# 09_Misc.net
KiCad netlist of a schematic drawn in Altium Designer
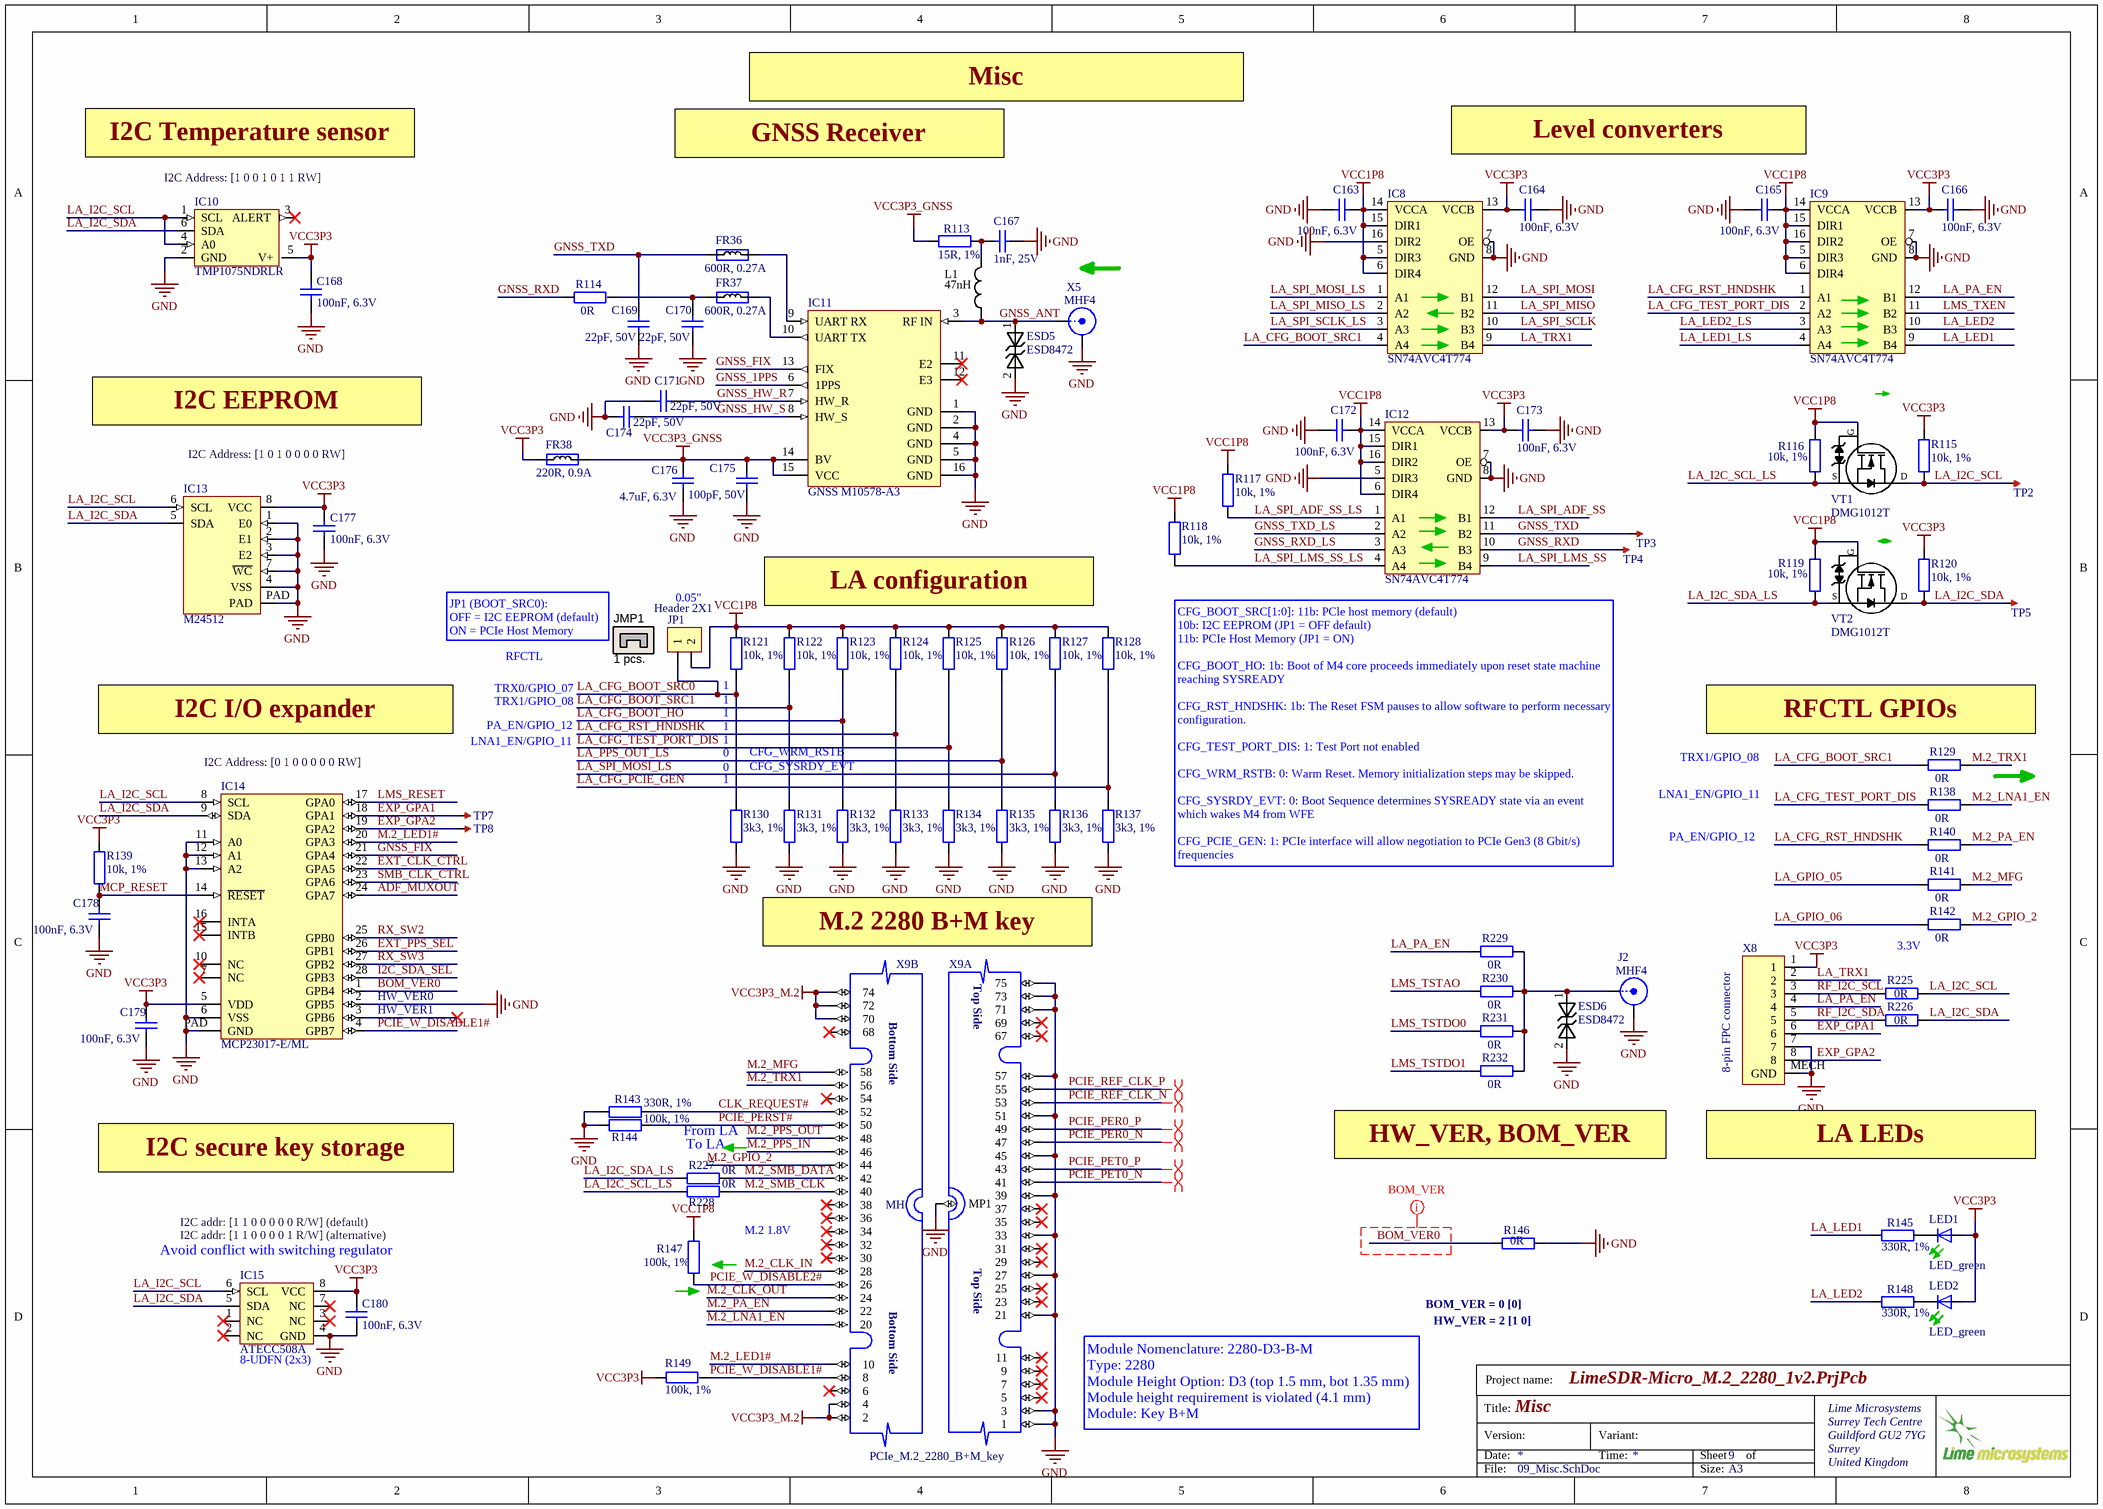
[diagram p0: 09_Misc.SchDoc]

(export (version "E")
  (design (tool "Eeschema 10.0.6"))
  (components
    (comp (ref "C163")
      (value "100nF, 6.3V")
      (footprint "CAP0201")
      (fields (field (name "MANUFACTURER") "Samsung") (field (name "TOLERANCE") "20%"))
      (libsource (lib "LimeMicroAltiumLib_schLib") (part "Cap_0402"))
    )
    (comp (ref "C164")
      (value "100nF, 6.3V")
      (footprint "CAP0201")
      (fields (field (name "MANUFACTURER") "Samsung") (field (name "TOLERANCE") "20%"))
      (libsource (lib "LimeMicroAltiumLib_schLib") (part "Cap_0402"))
    )
    (comp (ref "C165")
      (value "100nF, 6.3V")
      (footprint "CAP0201")
      (fields (field (name "MANUFACTURER") "Samsung") (field (name "TOLERANCE") "20%"))
      (libsource (lib "LimeMicroAltiumLib_schLib") (part "Cap_0402"))
    )
    (comp (ref "C166")
      (value "100nF, 6.3V")
      (footprint "CAP0201")
      (fields (field (name "MANUFACTURER") "Samsung") (field (name "TOLERANCE") "20%"))
      (libsource (lib "LimeMicroAltiumLib_schLib") (part "Cap_0402"))
    )
    (comp (ref "C167")
      (value "1nF, 25V")
      (footprint "CAP0201")
      (fields (field (name "TOLERANCE") "±10%") (field (name "MANUFACTURER") "TDK Corporation"))
      (libsource (lib "LimeMicroAltiumLib_schLib") (part "Cap_0402"))
    )
    (comp (ref "C168")
      (value "100nF, 6.3V")
      (footprint "CAP0201")
      (fields (field (name "MANUFACTURER") "Samsung") (field (name "TOLERANCE") "20%"))
      (libsource (lib "LimeMicroAltiumLib_schLib") (part "Cap_0402"))
    )
    (comp (ref "C169")
      (value "22pF, 50V")
      (footprint "CAP0201")
      (fields
        (field (name "MANUFACTURER") "Murata")
        (field (name "TOLERANCE") "5%")
        (field (name "VOLTAGE") "50V")
      )
      (libsource (lib "LimeMicroAltiumLib_schLib") (part "Cap_0402"))
    )
    (comp (ref "C170")
      (value "22pF, 50V")
      (footprint "CAP0201")
      (fields
        (field (name "MANUFACTURER") "Murata")
        (field (name "TOLERANCE") "5%")
        (field (name "VOLTAGE") "50V")
      )
      (libsource (lib "LimeMicroAltiumLib_schLib") (part "Cap_0402"))
    )
    (comp (ref "C171")
      (value "22pF, 50V")
      (footprint "CAP0201")
      (fields
        (field (name "MANUFACTURER") "Murata")
        (field (name "TOLERANCE") "5%")
        (field (name "VOLTAGE") "50V")
      )
      (libsource (lib "LimeMicroAltiumLib_schLib") (part "Cap_0402"))
    )
    (comp (ref "C172")
      (value "100nF, 6.3V")
      (footprint "CAP0201")
      (fields (field (name "MANUFACTURER") "Samsung") (field (name "TOLERANCE") "20%"))
      (libsource (lib "LimeMicroAltiumLib_schLib") (part "Cap_0402"))
    )
    (comp (ref "C173")
      (value "100nF, 6.3V")
      (footprint "CAP0201")
      (fields (field (name "MANUFACTURER") "Samsung") (field (name "TOLERANCE") "20%"))
      (libsource (lib "LimeMicroAltiumLib_schLib") (part "Cap_0402"))
    )
    (comp (ref "C174")
      (value "22pF, 50V")
      (footprint "CAP0201")
      (fields
        (field (name "MANUFACTURER") "Murata")
        (field (name "TOLERANCE") "5%")
        (field (name "VOLTAGE") "50V")
      )
      (libsource (lib "LimeMicroAltiumLib_schLib") (part "Cap_0402"))
    )
    (comp (ref "C175")
      (value "100pF, 50V")
      (footprint "CAP0201")
      (fields
        (field (name "MANUFACTURER") "TDK")
        (field (name "TOLERANCE") "5%")
        (field (name "VOLTAGE") "50V")
      )
      (libsource (lib "LimeMicroAltiumLib_schLib") (part "Cap_0402"))
    )
    (comp (ref "C176")
      (value "4.7uF, 6.3V")
      (footprint "CAP0402")
      (fields
        (field (name "MANUFACTURER") "Murata Electronics North America")
        (field (name "TOLERANCE") "±20%")
      )
      (libsource (lib "LimeMicroAltiumLib_schLib") (part "Cap_0402"))
    )
    (comp (ref "C177")
      (value "100nF, 6.3V")
      (footprint "CAP0201")
      (fields (field (name "MANUFACTURER") "Samsung") (field (name "TOLERANCE") "20%"))
      (libsource (lib "LimeMicroAltiumLib_schLib") (part "Cap_0402"))
    )
    (comp (ref "C178")
      (value "100nF, 6.3V")
      (footprint "CAP0201")
      (fields (field (name "MANUFACTURER") "Samsung") (field (name "TOLERANCE") "20%"))
      (libsource (lib "LimeMicroAltiumLib_schLib") (part "Cap_0402"))
    )
    (comp (ref "C179")
      (value "100nF, 6.3V")
      (footprint "CAP0201")
      (fields (field (name "MANUFACTURER") "Samsung") (field (name "TOLERANCE") "20%"))
      (libsource (lib "LimeMicroAltiumLib_schLib") (part "Cap_0402"))
    )
    (comp (ref "C180")
      (value "100nF, 6.3V")
      (footprint "CAP0201")
      (fields (field (name "MANUFACTURER") "Samsung") (field (name "TOLERANCE") "20%"))
      (libsource (lib "LimeMicroAltiumLib_schLib") (part "Cap_0402"))
    )
    (comp (ref "ESD5")
      (value "ESD8472")
      (footprint "ESD8472_X3DFN2")
      (fields (field (name "MANUFACTURER") "ON Semiconductor"))
      (libsource (lib "LimeMicroAltiumLib_schLib") (part "ESD8472"))
    )
    (comp (ref "ESD6")
      (value "ESD8472")
      (footprint "ESD8472_X3DFN2")
      (fields (field (name "MANUFACTURER") "ON Semiconductor"))
      (libsource (lib "LimeMicroAltiumLib_schLib") (part "ESD8472"))
    )
    (comp (ref "FR36")
      (value "600R, 0.27A")
      (footprint "RES0201")
      (fields (field (name "MANUFACTURER") "Taiyo Yuden"))
      (libsource (lib "LimeMicroAltiumLib_schLib") (part "Ferrite"))
    )
    (comp (ref "FR37")
      (value "600R, 0.27A")
      (footprint "RES0201")
      (fields (field (name "MANUFACTURER") "Taiyo Yuden"))
      (libsource (lib "LimeMicroAltiumLib_schLib") (part "Ferrite"))
    )
    (comp (ref "FR38")
      (value "220R, 0.9A")
      (footprint "RES0402")
      (fields (field (name "MANUFACTURER") "TDK Corporation"))
      (libsource (lib "LimeFPGAboard_schLib") (part "Ferrite"))
    )
    (comp (ref "IC8")
      (value "SN74AVC4T774")
      (footprint "SN74AVC4T774_v1")
      (fields (field (name "MANUFACTURER") "Texas Instruments"))
      (libsource (lib "LimeMicroAltiumLib") (part "SN74AVC4T774"))
    )
    (comp (ref "IC9")
      (value "SN74AVC4T774")
      (footprint "SN74AVC4T774_v1")
      (fields (field (name "MANUFACTURER") "Texas Instruments"))
      (libsource (lib "LimeMicroAltiumLib") (part "SN74AVC4T774"))
    )
    (comp (ref "IC10")
      (value "TMP1075NDRLR")
      (footprint "TMP1075NDRLR_temperature_sensor_SOT563")
      (fields (field (name "MANUFACTURER") "Texas Instruments"))
      (libsource (lib "LimeMicroAltiumLib_schLib_r04") (part "TMP1075NDRLR_temperature_sensor"))
    )
    (comp (ref "IC11")
      (value "GNSS M10578-A3")
      (footprint "M10578-A3_v2")
      (fields (field (name "MANUFACTURER") "Antenova"))
      (libsource (lib "LimeMicroAltiumLib_schLib_r04") (part "M10578-A3_GPS_GNSS"))
    )
    (comp (ref "IC12")
      (value "SN74AVC4T774")
      (footprint "SN74AVC4T774_v1")
      (fields (field (name "MANUFACTURER") "Texas Instruments"))
      (libsource (lib "LimeMicroAltiumLib") (part "SN74AVC4T774"))
    )
    (comp (ref "IC13")
      (value "M24512")
      (footprint "M24128-DFMC6TG")
      (fields (field (name "MANUFACTURER") "STMicroelectronics"))
      (libsource (lib "LimeMicroAltiumLib_schLib") (part "M24128-DFMC6TG"))
    )
    (comp (ref "IC14")
      (value "MCP23017-E/ML")
      (footprint "MCP23017-E/ML_QFN28")
      (fields (field (name "MANUFACTURER") "Microchip"))
      (libsource (lib "LimeMicroAltiumLib") (part "MCP23017-E/ML_I2C_expander"))
    )
    (comp (ref "IC15")
      (value "ATECC508A")
      (footprint "LimeMicroAltiumLib:ATECC508A_UDFN8_v2")
      (fields (field (name "MANUFACTURER") "Microchip"))
      (libsource (lib "LimeMicroAltiumLib_schLib_r01") (part "ATECC508A_authentication_IC"))
    )
    (comp (ref "J2")
      (value "MHF4")
      (footprint "IPEX_MHF4_conn")
      (description "IPEX MHF4 Connector Jack, Male Pin 50 Ohms Surface Mount Solder")
      (fields (field (name "MANUFACTURER") "TE Connectivity / Linx Technologies"))
      (libsource (lib "LimeMicroAltiumLib_schLib") (part "RF_IF_connector"))
    )
    (comp (ref "JMP1")
      (value "1 pcs.")
      (footprint "MECH_JUMPER_HALF_PITCH")
      (description "Shorting Jumper, 2-position, 1.27mm pitch")
      (fields (field (name "MANUFACTURER") "Sullins"))
      (libsource (lib "LimeMicroAltiumLib_schLib") (part "JUMP_2P_CONN_HEADER"))
    )
    (comp (ref "JP1")
      (value "Header 2X1")
      (footprint "HEADER_2x1_TH_HALF_PITCH")
      (fields (field (name "MANUFACTURER") "Harwin"))
      (libsource (lib "LimeMicroAltiumLib") (part "Header_2X1"))
    )
    (comp (ref "L1")
      (value "47nH")
      (footprint "RES0402")
      (fields
        (field (name "MANUFACTURER") "COILCRAFT")
        (field (name "MANUFACTURER PART NUMBER") "0402HP-47NXJLU")
      )
      (libsource (lib "LimeMicroAltiumLib_schLib") (part "Inductor_0603"))
    )
    (comp (ref "LED1")
      (value "LED_green")
      (footprint "LED0201")
      (fields (field (name "MANUFACTURER") "Kingbright"))
      (libsource (lib "LimeFPGAboard_schLib") (part "LED_green"))
    )
    (comp (ref "LED2")
      (value "LED_green")
      (footprint "LED0201")
      (fields (field (name "MANUFACTURER") "Kingbright"))
      (libsource (lib "LimeFPGAboard_schLib") (part "LED_green"))
    )
    (comp (ref "R113")
      (value "15R, 1%")
      (footprint "RES0201")
      (fields (field (name "MANUFACTURER") "Yageo") (field (name "TOLERANCE") "1%"))
      (libsource (lib "LimeFPGAboard_schLib") (part "Res_0402"))
    )
    (comp (ref "R114")
      (value "0R")
      (footprint "RES0201")
      (fields (field (name "MANUFACTURER") "Yageo") (field (name "TOLERANCE") "5%"))
      (libsource (lib "LimeFPGAboard_schLib") (part "Res_0402"))
    )
    (comp (ref "R115")
      (value "10k, 1%")
      (footprint "RES0201")
      (fields (field (name "MANUFACTURER") "Yageo") (field (name "TOLERANCE") "1%"))
      (libsource (lib "LimeFPGAboard_schLib") (part "Res_0402"))
    )
    (comp (ref "R116")
      (value "10k, 1%")
      (footprint "RES0201")
      (fields (field (name "MANUFACTURER") "Yageo") (field (name "TOLERANCE") "1%"))
      (libsource (lib "LimeFPGAboard_schLib") (part "Res_0402"))
    )
    (comp (ref "R117")
      (value "10k, 1%")
      (footprint "RES0201")
      (fields (field (name "MANUFACTURER") "Yageo") (field (name "TOLERANCE") "1%"))
      (libsource (lib "LimeFPGAboard_schLib") (part "Res_0402"))
    )
    (comp (ref "R118")
      (value "10k, 1%")
      (footprint "RES0201")
      (fields (field (name "MANUFACTURER") "Yageo") (field (name "TOLERANCE") "1%"))
      (libsource (lib "LimeFPGAboard_schLib") (part "Res_0402"))
    )
    (comp (ref "R119")
      (value "10k, 1%")
      (footprint "RES0201")
      (fields (field (name "MANUFACTURER") "Yageo") (field (name "TOLERANCE") "1%"))
      (libsource (lib "LimeFPGAboard_schLib") (part "Res_0402"))
    )
    (comp (ref "R120")
      (value "10k, 1%")
      (footprint "RES0201")
      (fields (field (name "MANUFACTURER") "Yageo") (field (name "TOLERANCE") "1%"))
      (libsource (lib "LimeFPGAboard_schLib") (part "Res_0402"))
    )
    (comp (ref "R121")
      (value "10k, 1%")
      (footprint "RES0201")
      (fields (field (name "MANUFACTURER") "Yageo") (field (name "TOLERANCE") "1%"))
      (libsource (lib "LimeFPGAboard_schLib") (part "Res_0402"))
    )
    (comp (ref "R122")
      (value "10k, 1%")
      (footprint "RES0201")
      (fields (field (name "MANUFACTURER") "Yageo") (field (name "TOLERANCE") "1%"))
      (libsource (lib "LimeFPGAboard_schLib") (part "Res_0402"))
    )
    (comp (ref "R123")
      (value "10k, 1%")
      (footprint "RES0201")
      (fields (field (name "MANUFACTURER") "Yageo") (field (name "TOLERANCE") "1%"))
      (libsource (lib "LimeFPGAboard_schLib") (part "Res_0402"))
    )
    (comp (ref "R124")
      (value "10k, 1%")
      (footprint "RES0201")
      (fields (field (name "MANUFACTURER") "Yageo") (field (name "TOLERANCE") "1%"))
      (libsource (lib "LimeFPGAboard_schLib") (part "Res_0402"))
    )
    (comp (ref "R125")
      (value "10k, 1%")
      (footprint "RES0201")
      (fields (field (name "MANUFACTURER") "Yageo") (field (name "TOLERANCE") "1%"))
      (libsource (lib "LimeFPGAboard_schLib") (part "Res_0402"))
    )
    (comp (ref "R126")
      (value "10k, 1%")
      (footprint "RES0201")
      (fields (field (name "MANUFACTURER") "Yageo") (field (name "TOLERANCE") "1%"))
      (libsource (lib "LimeFPGAboard_schLib") (part "Res_0402"))
    )
    (comp (ref "R127")
      (value "10k, 1%")
      (footprint "RES0201")
      (fields (field (name "MANUFACTURER") "Yageo") (field (name "TOLERANCE") "1%"))
      (libsource (lib "LimeFPGAboard_schLib") (part "Res_0402"))
    )
    (comp (ref "R128")
      (value "10k, 1%")
      (footprint "RES0201")
      (fields (field (name "MANUFACTURER") "Yageo") (field (name "TOLERANCE") "1%"))
      (libsource (lib "LimeFPGAboard_schLib") (part "Res_0402"))
    )
    (comp (ref "R129")
      (value "0R")
      (footprint "RES0201")
      (fields (field (name "MANUFACTURER") "Yageo") (field (name "TOLERANCE") "5%"))
      (libsource (lib "LimeFPGAboard_schLib") (part "Res_0402"))
    )
    (comp (ref "R130")
      (value "3k3, 1%")
      (footprint "RES0201")
      (fields (field (name "MANUFACTURER") "Yageo") (field (name "TOLERANCE") "1%"))
      (libsource (lib "LimeFPGAboard_schLib") (part "Res_0402"))
    )
    (comp (ref "R131")
      (value "3k3, 1%")
      (footprint "RES0201")
      (fields (field (name "MANUFACTURER") "Yageo") (field (name "TOLERANCE") "1%"))
      (libsource (lib "LimeFPGAboard_schLib") (part "Res_0402"))
    )
    (comp (ref "R132")
      (value "3k3, 1%")
      (footprint "RES0201")
      (fields (field (name "MANUFACTURER") "Yageo") (field (name "TOLERANCE") "1%"))
      (libsource (lib "LimeFPGAboard_schLib") (part "Res_0402"))
    )
    (comp (ref "R133")
      (value "3k3, 1%")
      (footprint "RES0201")
      (fields (field (name "MANUFACTURER") "Yageo") (field (name "TOLERANCE") "1%"))
      (libsource (lib "LimeFPGAboard_schLib") (part "Res_0402"))
    )
    (comp (ref "R134")
      (value "3k3, 1%")
      (footprint "RES0201")
      (fields (field (name "MANUFACTURER") "Yageo") (field (name "TOLERANCE") "1%"))
      (libsource (lib "LimeFPGAboard_schLib") (part "Res_0402"))
    )
    (comp (ref "R135")
      (value "3k3, 1%")
      (footprint "RES0201")
      (fields (field (name "MANUFACTURER") "Yageo") (field (name "TOLERANCE") "1%"))
      (libsource (lib "LimeFPGAboard_schLib") (part "Res_0402"))
    )
    (comp (ref "R136")
      (value "3k3, 1%")
      (footprint "RES0201")
      (fields (field (name "MANUFACTURER") "Yageo") (field (name "TOLERANCE") "1%"))
      (libsource (lib "LimeFPGAboard_schLib") (part "Res_0402"))
    )
    (comp (ref "R137")
      (value "3k3, 1%")
      (footprint "RES0201")
      (fields (field (name "MANUFACTURER") "Yageo") (field (name "TOLERANCE") "1%"))
      (libsource (lib "LimeFPGAboard_schLib") (part "Res_0402"))
    )
    (comp (ref "R138")
      (value "0R")
      (footprint "RES0201")
      (fields (field (name "MANUFACTURER") "Yageo") (field (name "TOLERANCE") "5%"))
      (libsource (lib "LimeFPGAboard_schLib") (part "Res_0402"))
    )
    (comp (ref "R139")
      (value "10k, 1%")
      (footprint "RES0201")
      (fields (field (name "MANUFACTURER") "Yageo") (field (name "TOLERANCE") "1%"))
      (libsource (lib "LimeFPGAboard_schLib") (part "Res_0402"))
    )
    (comp (ref "R140")
      (value "0R")
      (footprint "RES0201")
      (fields (field (name "MANUFACTURER") "Yageo") (field (name "TOLERANCE") "5%"))
      (libsource (lib "LimeFPGAboard_schLib") (part "Res_0402"))
    )
    (comp (ref "R141")
      (value "0R")
      (footprint "RES0201")
      (fields (field (name "MANUFACTURER") "Yageo") (field (name "TOLERANCE") "5%"))
      (libsource (lib "LimeFPGAboard_schLib") (part "Res_0402"))
    )
    (comp (ref "R142")
      (value "0R")
      (footprint "RES0201")
      (fields (field (name "MANUFACTURER") "Yageo") (field (name "TOLERANCE") "5%"))
      (libsource (lib "LimeFPGAboard_schLib") (part "Res_0402"))
    )
    (comp (ref "R143")
      (value "330R, 1%")
      (footprint "RES0201")
      (fields (field (name "MANUFACTURER") "Vishay Dale") (field (name "TOLERANCE") "1%"))
      (libsource (lib "LimeFPGAboard_schLib") (part "Res_0402"))
    )
    (comp (ref "R144")
      (value "100k, 1%")
      (footprint "RES0201")
      (fields (field (name "MANUFACTURER") "Yageo") (field (name "TOLERANCE") "1%"))
      (libsource (lib "LimeMicroAltiumLib_schLib") (part "Res_0402"))
    )
    (comp (ref "R145")
      (value "330R, 1%")
      (footprint "RES0201")
      (fields (field (name "MANUFACTURER") "Vishay Dale") (field (name "TOLERANCE") "1%"))
      (libsource (lib "LimeFPGAboard_schLib") (part "Res_0402"))
    )
    (comp (ref "R146")
      (value "0R")
      (footprint "RES0201")
      (fields (field (name "MANUFACTURER") "Yageo") (field (name "TOLERANCE") "5%"))
      (libsource (lib "LimeFPGAboard_schLib") (part "Res_0402"))
    )
    (comp (ref "R147")
      (value "100k, 1%")
      (footprint "RES0201")
      (fields (field (name "MANUFACTURER") "Yageo") (field (name "TOLERANCE") "1%"))
      (libsource (lib "LimeMicroAltiumLib_schLib") (part "Res_0402"))
    )
    (comp (ref "R148")
      (value "330R, 1%")
      (footprint "RES0201")
      (fields (field (name "MANUFACTURER") "Vishay Dale") (field (name "TOLERANCE") "1%"))
      (libsource (lib "LimeFPGAboard_schLib") (part "Res_0402"))
    )
    (comp (ref "R149")
      (value "100k, 1%")
      (footprint "RES0201")
      (fields (field (name "MANUFACTURER") "Yageo") (field (name "TOLERANCE") "1%"))
      (libsource (lib "LimeMicroAltiumLib_schLib") (part "Res_0402"))
    )
    (comp (ref "R225")
      (value "0R")
      (footprint "RES0201")
      (fields (field (name "MANUFACTURER") "Yageo") (field (name "TOLERANCE") "5%"))
      (libsource (lib "LimeFPGAboard_schLib") (part "Res_0402"))
    )
    (comp (ref "R226")
      (value "0R")
      (footprint "RES0201")
      (fields (field (name "MANUFACTURER") "Yageo") (field (name "TOLERANCE") "5%"))
      (libsource (lib "LimeFPGAboard_schLib") (part "Res_0402"))
    )
    (comp (ref "R227")
      (value "0R")
      (footprint "RES0201")
      (fields (field (name "MANUFACTURER") "Yageo") (field (name "TOLERANCE") "5%"))
      (libsource (lib "LimeFPGAboard_schLib") (part "Res_0402"))
    )
    (comp (ref "R228")
      (value "0R")
      (footprint "RES0201")
      (fields (field (name "MANUFACTURER") "Yageo") (field (name "TOLERANCE") "5%"))
      (libsource (lib "LimeFPGAboard_schLib") (part "Res_0402"))
    )
    (comp (ref "R229")
      (value "0R")
      (footprint "RES0201")
      (fields (field (name "MANUFACTURER") "Yageo") (field (name "TOLERANCE") "5%"))
      (libsource (lib "LimeFPGAboard_schLib") (part "Res_0402"))
    )
    (comp (ref "R230")
      (value "0R")
      (footprint "RES0201")
      (fields (field (name "MANUFACTURER") "Yageo") (field (name "TOLERANCE") "5%"))
      (libsource (lib "LimeFPGAboard_schLib") (part "Res_0402"))
    )
    (comp (ref "R231")
      (value "0R")
      (footprint "RES0201")
      (fields (field (name "MANUFACTURER") "Yageo") (field (name "TOLERANCE") "5%"))
      (libsource (lib "LimeFPGAboard_schLib") (part "Res_0402"))
    )
    (comp (ref "R232")
      (value "0R")
      (footprint "RES0201")
      (fields (field (name "MANUFACTURER") "Yageo") (field (name "TOLERANCE") "5%"))
      (libsource (lib "LimeFPGAboard_schLib") (part "Res_0402"))
    )
    (comp (ref "TP2")
      (value "TESTPOINT_PAD")
      (footprint "TP_PAD_1MM")
      (description "Test Point PCB mount Miniature White")
      (libsource (lib "LimeMicroAltiumLib_schLib_r04") (part "TESTPOINT_PAD"))
    )
    (comp (ref "TP3")
      (value "TESTPOINT_PAD")
      (footprint "TP_PAD_1MM")
      (description "Test Point PCB mount Miniature White")
      (libsource (lib "LimeMicroAltiumLib_schLib_r04") (part "TESTPOINT_PAD"))
    )
    (comp (ref "TP4")
      (value "TESTPOINT_PAD")
      (footprint "TP_PAD_1MM")
      (description "Test Point PCB mount Miniature White")
      (libsource (lib "LimeMicroAltiumLib_schLib_r04") (part "TESTPOINT_PAD"))
    )
    (comp (ref "TP5")
      (value "TESTPOINT_PAD")
      (footprint "TP_PAD_1MM")
      (description "Test Point PCB mount Miniature White")
      (libsource (lib "LimeMicroAltiumLib_schLib_r04") (part "TESTPOINT_PAD"))
    )
    (comp (ref "TP7")
      (value "TESTPOINT_PAD")
      (footprint "TP_PAD_1MM")
      (description "Test Point PCB mount Miniature White")
      (libsource (lib "LimeMicroAltiumLib_schLib_r04") (part "TESTPOINT_PAD"))
    )
    (comp (ref "TP8")
      (value "TESTPOINT_PAD")
      (footprint "TP_PAD_1MM")
      (description "Test Point PCB mount Miniature White")
      (libsource (lib "LimeMicroAltiumLib_schLib_r04") (part "TESTPOINT_PAD"))
    )
    (comp (ref "VT1")
      (value "DMG1012T")
      (footprint "SOT523")
      (fields (field (name "MANUFACTURER") "Diodes Incorporated"))
      (libsource (lib "LimeMicroAltiumLib_schLib_r01") (part "DMG1012T"))
    )
    (comp (ref "VT2")
      (value "DMG1012T")
      (footprint "SOT523")
      (fields (field (name "MANUFACTURER") "Diodes Incorporated"))
      (libsource (lib "LimeMicroAltiumLib_schLib_r01") (part "DMG1012T"))
    )
    (comp (ref "X5")
      (value "MHF4")
      (footprint "IPEX_MHF4_conn")
      (description "IPEX MHF4 Connector Jack, Male Pin 50 Ohms Surface Mount Solder")
      (fields (field (name "MANUFACTURER") "TE Connectivity / Linx Technologies"))
      (libsource (lib "LimeMicroAltiumLib_schLib") (part "RF_IF_connector"))
    )
    (comp (ref "X8")
      (value "8-pin FPC connector")
      (footprint "503480-0800_8PIN_FPC_CONN")
      (fields (field (name "MANUFACTURER") "Molex"))
      (libsource (lib "LimeMicroAltiumLib_schLib_r04") (part "503480-0800_8PIN_FPC_CONN"))
    )
    (comp (ref "X9")
      (value "PCIe_M.2_2280_B+M_key")
      (footprint "PCIe_M.2_2280_B+M_key")
      (libsource (lib "LimeMicroAltiumLib") (part "PCIe_M.2_2280_B+M_key"))
    )
  )
  (nets
    (net (code "1") (name "/ADF_MUXOUT") (class "Default")
      (node (ref "IC14") (pin "24") (pinfunction "GPA7_24") (pintype "bidirectional"))
    )
    (net (code "2") (name "/BOM_VER0") (class "Default")
      (node (ref "IC14") (pin "1") (pinfunction "GPB4_1") (pintype "bidirectional"))
      (node (ref "R146") (pin "1") (pinfunction "1_1") (pintype "passive"))
    )
    (net (code "3") (name "/CLK_REQUEST#") (class "Default")
      (node (ref "R143") (pin "1") (pinfunction "1_1") (pintype "passive"))
      (node (ref "X9") (pin "P52") (pinfunction "52_P52") (pintype "bidirectional"))
    )
    (net (code "4") (name "/EXP_GPA1") (class "Default")
      (node (ref "IC14") (pin "18") (pinfunction "GPA1_18") (pintype "bidirectional"))
      (node (ref "TP7") (pin "1") (pintype "passive"))
      (node (ref "X8") (pin "6") (pinfunction "6_6") (pintype "passive"))
    )
    (net (code "5") (name "/EXP_GPA2") (class "Default")
      (node (ref "IC14") (pin "19") (pinfunction "GPA2_19") (pintype "bidirectional"))
      (node (ref "TP8") (pin "1") (pintype "passive"))
      (node (ref "X8") (pin "8") (pinfunction "8_8") (pintype "passive"))
    )
    (net (code "6") (name "/EXT_CLK_CTRL") (class "Default")
      (node (ref "IC14") (pin "22") (pinfunction "GPA5_22") (pintype "bidirectional"))
    )
    (net (code "7") (name "/EXT_PPS_SEL") (class "Default")
      (node (ref "IC14") (pin "26") (pinfunction "GPB1_26") (pintype "bidirectional"))
    )
    (net (code "8") (name "/GNSS_1PPS") (class "Default")
      (node (ref "IC11") (pin "6") (pinfunction "1PPS_6") (pintype "output"))
    )
    (net (code "9") (name "/GNSS_ANT") (class "Default")
      (node (ref "ESD5") (pin "1") (pinfunction "1_1") (pintype "passive"))
      (node (ref "IC11") (pin "3") (pinfunction "RF_IN_3") (pintype "input"))
      (node (ref "L1") (pin "1") (pinfunction "1_1") (pintype "passive"))
      (node (ref "X5") (pin "1") (pinfunction "X_1") (pintype "passive"))
    )
    (net (code "10") (name "/GNSS_FIX") (class "Default")
      (node (ref "IC11") (pin "13") (pinfunction "FIX_13") (pintype "output"))
      (node (ref "IC14") (pin "21") (pinfunction "GPA4_21") (pintype "bidirectional"))
    )
    (net (code "11") (name "/GNSS_HW_R") (class "Default")
      (node (ref "C171") (pin "1") (pinfunction "1_1") (pintype "passive"))
      (node (ref "IC11") (pin "7") (pinfunction "HW_R_7") (pintype "input"))
    )
    (net (code "12") (name "/GNSS_HW_S") (class "Default")
      (node (ref "C174") (pin "1") (pinfunction "1_1") (pintype "passive"))
      (node (ref "IC11") (pin "8") (pinfunction "HW_S_8") (pintype "input"))
    )
    (net (code "13") (name "/GNSS_RXD") (class "Default")
      (node (ref "IC12") (pin "10") (pinfunction "B3_10") (pintype "passive"))
      (node (ref "R114") (pin "1") (pinfunction "1_1") (pintype "passive"))
      (node (ref "TP4") (pin "1") (pintype "passive"))
    )
    (net (code "14") (name "/GNSS_RXD_LS") (class "Default")
      (node (ref "IC12") (pin "3") (pinfunction "A3_3") (pintype "passive"))
    )
    (net (code "15") (name "/GNSS_TXD") (class "Default")
      (node (ref "C169") (pin "1") (pinfunction "1_1") (pintype "passive"))
      (node (ref "FR36") (pin "1") (pinfunction "1_1") (pintype "passive"))
      (node (ref "IC12") (pin "11") (pinfunction "B2_11") (pintype "passive"))
      (node (ref "TP3") (pin "1") (pintype "passive"))
    )
    (net (code "16") (name "/GNSS_TXD_LS") (class "Default")
      (node (ref "IC12") (pin "2") (pinfunction "A2_2") (pintype "passive"))
    )
    (net (code "17") (name "/I2C_SDA_SEL") (class "Default")
      (node (ref "IC14") (pin "28") (pinfunction "GPB3_28") (pintype "bidirectional"))
    )
    (net (code "18") (name "/LA_CFG_BOOT_HO") (class "Default")
      (node (ref "R123") (pin "2") (pinfunction "2_2") (pintype "passive"))
      (node (ref "R132") (pin "1") (pinfunction "1_1") (pintype "passive"))
    )
    (net (code "19") (name "/LA_CFG_BOOT_SRC0") (class "Default")
      (node (ref "JP1") (pin "1") (pinfunction "1_1") (pintype "passive"))
      (node (ref "R121") (pin "2") (pinfunction "2_2") (pintype "passive"))
      (node (ref "R130") (pin "1") (pinfunction "1_1") (pintype "passive"))
    )
    (net (code "20") (name "/LA_CFG_BOOT_SRC1") (class "Default")
      (node (ref "IC8") (pin "4") (pinfunction "A4_4") (pintype "passive"))
      (node (ref "R122") (pin "2") (pinfunction "2_2") (pintype "passive"))
      (node (ref "R129") (pin "1") (pinfunction "1_1") (pintype "passive"))
      (node (ref "R131") (pin "1") (pinfunction "1_1") (pintype "passive"))
    )
    (net (code "21") (name "/LA_CFG_PCIE_GEN") (class "Default")
      (node (ref "R128") (pin "2") (pinfunction "2_2") (pintype "passive"))
      (node (ref "R137") (pin "1") (pinfunction "1_1") (pintype "passive"))
    )
    (net (code "22") (name "/LA_CFG_RST_HNDSHK") (class "Default")
      (node (ref "IC9") (pin "1") (pinfunction "A1_1") (pintype "passive"))
      (node (ref "R124") (pin "2") (pinfunction "2_2") (pintype "passive"))
      (node (ref "R133") (pin "1") (pinfunction "1_1") (pintype "passive"))
      (node (ref "R140") (pin "1") (pinfunction "1_1") (pintype "passive"))
    )
    (net (code "23") (name "/LA_CFG_TEST_PORT_DIS") (class "Default")
      (node (ref "IC9") (pin "2") (pinfunction "A2_2") (pintype "passive"))
      (node (ref "R125") (pin "2") (pinfunction "2_2") (pintype "passive"))
      (node (ref "R134") (pin "1") (pinfunction "1_1") (pintype "passive"))
      (node (ref "R138") (pin "1") (pinfunction "1_1") (pintype "passive"))
    )
    (net (code "24") (name "/LA_GPIO_05") (class "Default")
      (node (ref "R141") (pin "1") (pinfunction "1_1") (pintype "passive"))
    )
    (net (code "25") (name "/LA_GPIO_06") (class "Default")
      (node (ref "R142") (pin "1") (pinfunction "1_1") (pintype "passive"))
    )
    (net (code "26") (name "/LA_I2C_SCL") (class "Default")
      (node (ref "IC10") (pin "1") (pinfunction "SCL_1") (pintype "input"))
      (node (ref "IC10") (pin "4") (pinfunction "A0_4") (pintype "input"))
      (node (ref "IC13") (pin "6") (pinfunction "SCL_6") (pintype "input"))
      (node (ref "IC14") (pin "8") (pinfunction "SCL_8") (pintype "input"))
      (node (ref "IC15") (pin "6") (pinfunction "SCL_6") (pintype "input"))
      (node (ref "R115") (pin "2") (pinfunction "2_2") (pintype "passive"))
      (node (ref "R225") (pin "2") (pinfunction "2_2") (pintype "passive"))
      (node (ref "TP2") (pin "1") (pintype "passive"))
      (node (ref "VT1") (pin "D") (pinfunction "D_D") (pintype "passive"))
    )
    (net (code "27") (name "/LA_I2C_SCL_LS") (class "Default")
      (node (ref "R116") (pin "2") (pinfunction "2_2") (pintype "passive"))
      (node (ref "R228") (pin "1") (pinfunction "1_1") (pintype "passive"))
      (node (ref "VT1") (pin "S") (pinfunction "S_S") (pintype "passive"))
    )
    (net (code "28") (name "/LA_I2C_SDA") (class "Default")
      (node (ref "IC10") (pin "6") (pinfunction "SDA_6") (pintype "bidirectional"))
      (node (ref "IC13") (pin "5") (pinfunction "SDA_5") (pintype "bidirectional"))
      (node (ref "IC14") (pin "9") (pinfunction "SDA_9") (pintype "bidirectional"))
      (node (ref "IC15") (pin "5") (pinfunction "SDA_5") (pintype "bidirectional"))
      (node (ref "R120") (pin "2") (pinfunction "2_2") (pintype "passive"))
      (node (ref "R226") (pin "2") (pinfunction "2_2") (pintype "passive"))
      (node (ref "TP5") (pin "1") (pintype "passive"))
      (node (ref "VT2") (pin "D") (pinfunction "D_D") (pintype "passive"))
    )
    (net (code "29") (name "/LA_I2C_SDA_LS") (class "Default")
      (node (ref "R119") (pin "2") (pinfunction "2_2") (pintype "passive"))
      (node (ref "R227") (pin "1") (pinfunction "1_1") (pintype "passive"))
      (node (ref "VT2") (pin "S") (pinfunction "S_S") (pintype "passive"))
    )
    (net (code "30") (name "/LA_LED1") (class "Default")
      (node (ref "IC9") (pin "9") (pinfunction "B4_9") (pintype "passive"))
      (node (ref "R145") (pin "2") (pinfunction "2_2") (pintype "passive"))
    )
    (net (code "31") (name "/LA_LED1_LS") (class "Default")
      (node (ref "IC9") (pin "4") (pinfunction "A4_4") (pintype "passive"))
    )
    (net (code "32") (name "/LA_LED2") (class "Default")
      (node (ref "IC9") (pin "10") (pinfunction "B3_10") (pintype "passive"))
      (node (ref "R148") (pin "2") (pinfunction "2_2") (pintype "passive"))
    )
    (net (code "33") (name "/LA_LED2_LS") (class "Default")
      (node (ref "IC9") (pin "3") (pinfunction "A3_3") (pintype "passive"))
    )
    (net (code "34") (name "/LA_PA_EN") (class "Default")
      (node (ref "IC9") (pin "12") (pinfunction "B1_12") (pintype "passive"))
      (node (ref "R229") (pin "1") (pinfunction "1_1") (pintype "passive"))
      (node (ref "X8") (pin "4") (pinfunction "4_4") (pintype "passive"))
    )
    (net (code "35") (name "/LA_PPS_OUT_LS") (class "Default")
      (node (ref "R126") (pin "2") (pinfunction "2_2") (pintype "passive"))
      (node (ref "R135") (pin "1") (pinfunction "1_1") (pintype "passive"))
    )
    (net (code "36") (name "/LA_SPI_ADF_SS") (class "Default")
      (node (ref "IC12") (pin "12") (pinfunction "B1_12") (pintype "passive"))
    )
    (net (code "37") (name "/LA_SPI_ADF_SS_LS") (class "Default")
      (node (ref "IC12") (pin "1") (pinfunction "A1_1") (pintype "passive"))
      (node (ref "R117") (pin "2") (pinfunction "2_2") (pintype "passive"))
    )
    (net (code "38") (name "/LA_SPI_LMS_SS") (class "Default")
      (node (ref "IC12") (pin "9") (pinfunction "B4_9") (pintype "passive"))
    )
    (net (code "39") (name "/LA_SPI_LMS_SS_LS") (class "Default")
      (node (ref "IC12") (pin "4") (pinfunction "A4_4") (pintype "passive"))
      (node (ref "R118") (pin "2") (pinfunction "2_2") (pintype "passive"))
    )
    (net (code "40") (name "/LA_SPI_MISO") (class "Default")
      (node (ref "IC8") (pin "11") (pinfunction "B2_11") (pintype "passive"))
    )
    (net (code "41") (name "/LA_SPI_MISO_LS") (class "Default")
      (node (ref "IC8") (pin "2") (pinfunction "A2_2") (pintype "passive"))
    )
    (net (code "42") (name "/LA_SPI_MOSI") (class "Default")
      (node (ref "IC8") (pin "12") (pinfunction "B1_12") (pintype "passive"))
    )
    (net (code "43") (name "/LA_SPI_MOSI_LS") (class "Default")
      (node (ref "IC8") (pin "1") (pinfunction "A1_1") (pintype "passive"))
      (node (ref "R127") (pin "2") (pinfunction "2_2") (pintype "passive"))
      (node (ref "R136") (pin "1") (pinfunction "1_1") (pintype "passive"))
    )
    (net (code "44") (name "/LA_SPI_SCLK") (class "Default")
      (node (ref "IC8") (pin "10") (pinfunction "B3_10") (pintype "passive"))
    )
    (net (code "45") (name "/LA_SPI_SCLK_LS") (class "Default")
      (node (ref "IC8") (pin "3") (pinfunction "A3_3") (pintype "passive"))
    )
    (net (code "46") (name "/LA_TRX1") (class "Default")
      (node (ref "IC8") (pin "9") (pinfunction "B4_9") (pintype "passive"))
      (node (ref "X8") (pin "2") (pinfunction "2_2") (pintype "passive"))
    )
    (net (code "47") (name "/LMS_RESET") (class "Default")
      (node (ref "IC14") (pin "17") (pinfunction "GPA0_17") (pintype "bidirectional"))
    )
    (net (code "48") (name "/LMS_TSTAO") (class "Default")
      (node (ref "R230") (pin "1") (pinfunction "1_1") (pintype "passive"))
    )
    (net (code "49") (name "/LMS_TSTDO0") (class "Default")
      (node (ref "R231") (pin "1") (pinfunction "1_1") (pintype "passive"))
    )
    (net (code "50") (name "/LMS_TSTDO1") (class "Default")
      (node (ref "R232") (pin "1") (pinfunction "1_1") (pintype "passive"))
    )
    (net (code "51") (name "/LMS_TXEN") (class "Default")
      (node (ref "IC9") (pin "11") (pinfunction "B2_11") (pintype "passive"))
    )
    (net (code "52") (name "/M.2_CLK_IN") (class "Default")
      (node (ref "X9") (pin "P28") (pinfunction "28_P28") (pintype "bidirectional"))
    )
    (net (code "53") (name "/M.2_CLK_OUT") (class "Default")
      (node (ref "X9") (pin "P24") (pinfunction "24_P24") (pintype "bidirectional"))
    )
    (net (code "54") (name "/M.2_GPIO_2") (class "Default")
      (node (ref "R142") (pin "2") (pinfunction "2_2") (pintype "passive"))
      (node (ref "X9") (pin "P44") (pinfunction "44_P44") (pintype "bidirectional"))
    )
    (net (code "55") (name "/M.2_LED1#") (class "Default")
      (node (ref "IC14") (pin "20") (pinfunction "GPA3_20") (pintype "bidirectional"))
      (node (ref "X9") (pin "P10") (pinfunction "10_P10") (pintype "bidirectional"))
    )
    (net (code "56") (name "/M.2_LNA1_EN") (class "Default")
      (node (ref "R138") (pin "2") (pinfunction "2_2") (pintype "passive"))
      (node (ref "X9") (pin "P20") (pinfunction "20_P20") (pintype "bidirectional"))
    )
    (net (code "57") (name "/M.2_MFG") (class "Default")
      (node (ref "R141") (pin "2") (pinfunction "2_2") (pintype "passive"))
      (node (ref "X9") (pin "P58") (pinfunction "58_P58") (pintype "bidirectional"))
    )
    (net (code "58") (name "/M.2_PA_EN") (class "Default")
      (node (ref "R140") (pin "2") (pinfunction "2_2") (pintype "passive"))
      (node (ref "X9") (pin "P22") (pinfunction "22_P22") (pintype "bidirectional"))
    )
    (net (code "59") (name "/M.2_PPS_IN") (class "Default")
      (node (ref "X9") (pin "P46") (pinfunction "46_P46") (pintype "bidirectional"))
    )
    (net (code "60") (name "/M.2_PPS_OUT") (class "Default")
      (node (ref "X9") (pin "P48") (pinfunction "48_P48") (pintype "bidirectional"))
    )
    (net (code "61") (name "/M.2_SMB_CLK") (class "Default")
      (node (ref "R228") (pin "2") (pinfunction "2_2") (pintype "passive"))
      (node (ref "X9") (pin "P40") (pinfunction "40_P40") (pintype "bidirectional"))
    )
    (net (code "62") (name "/M.2_SMB_DATA") (class "Default")
      (node (ref "R227") (pin "2") (pinfunction "2_2") (pintype "passive"))
      (node (ref "X9") (pin "P42") (pinfunction "42_P42") (pintype "bidirectional"))
    )
    (net (code "63") (name "/M.2_TRX1") (class "Default")
      (node (ref "R129") (pin "2") (pinfunction "2_2") (pintype "passive"))
      (node (ref "X9") (pin "P56") (pinfunction "56_P56") (pintype "bidirectional"))
    )
    (net (code "64") (name "/MCP_RESET") (class "Default")
      (node (ref "C178") (pin "1") (pinfunction "1_1") (pintype "passive"))
      (node (ref "IC14") (pin "14") (pinfunction "~{RESET}_14") (pintype "input"))
      (node (ref "R139") (pin "2") (pinfunction "2_2") (pintype "passive"))
    )
    (net (code "65") (name "/PCIE_PER0_N") (class "Default")
      (node (ref "X9") (pin "P47") (pinfunction "47_P47") (pintype "bidirectional"))
    )
    (net (code "66") (name "/PCIE_PER0_P") (class "Default")
      (node (ref "X9") (pin "P49") (pinfunction "49_P49") (pintype "bidirectional"))
    )
    (net (code "67") (name "/PCIE_PERST#") (class "Default")
      (node (ref "R144") (pin "1") (pinfunction "1_1") (pintype "passive"))
      (node (ref "X9") (pin "P50") (pinfunction "50_P50") (pintype "bidirectional"))
    )
    (net (code "68") (name "/PCIE_PET0_N") (class "Default")
      (node (ref "X9") (pin "P41") (pinfunction "41_P41") (pintype "bidirectional"))
    )
    (net (code "69") (name "/PCIE_PET0_P") (class "Default")
      (node (ref "X9") (pin "P43") (pinfunction "43_P43") (pintype "bidirectional"))
    )
    (net (code "70") (name "/PCIE_REF_CLK_N") (class "Default")
      (node (ref "X9") (pin "P53") (pinfunction "53_P53") (pintype "bidirectional"))
    )
    (net (code "71") (name "/PCIE_REF_CLK_P") (class "Default")
      (node (ref "X9") (pin "P55") (pinfunction "55_P55") (pintype "bidirectional"))
    )
    (net (code "72") (name "/PCIE_W_DISABLE1#") (class "Default")
      (node (ref "IC14") (pin "4") (pinfunction "GPB7_4") (pintype "bidirectional"))
      (node (ref "R149") (pin "2") (pinfunction "2_2") (pintype "passive"))
      (node (ref "X9") (pin "P8") (pinfunction "8_P8") (pintype "bidirectional"))
    )
    (net (code "73") (name "/PCIE_W_DISABLE2#") (class "Default")
      (node (ref "R147") (pin "2") (pinfunction "2_2") (pintype "passive"))
      (node (ref "X9") (pin "P26") (pinfunction "26_P26") (pintype "bidirectional"))
    )
    (net (code "74") (name "/RF_I2C_SCL") (class "Default")
      (node (ref "R225") (pin "1") (pinfunction "1_1") (pintype "passive"))
      (node (ref "X8") (pin "3") (pinfunction "3_3") (pintype "passive"))
    )
    (net (code "75") (name "/RF_I2C_SDA") (class "Default")
      (node (ref "R226") (pin "1") (pinfunction "1_1") (pintype "passive"))
      (node (ref "X8") (pin "5") (pinfunction "5_5") (pintype "passive"))
    )
    (net (code "76") (name "/RX_SW2") (class "Default")
      (node (ref "IC14") (pin "25") (pinfunction "GPB0_25") (pintype "bidirectional"))
    )
    (net (code "77") (name "/RX_SW3") (class "Default")
      (node (ref "IC14") (pin "27") (pinfunction "GPB2_27") (pintype "bidirectional"))
    )
    (net (code "78") (name "/SMB_CLK_CTRL") (class "Default")
      (node (ref "IC14") (pin "23") (pinfunction "GPA6_23") (pintype "bidirectional"))
    )
    (net (code "79") (name "GND") (class "Default")
      (node (ref "C163") (pin "1") (pinfunction "1_1") (pintype "passive"))
      (node (ref "C164") (pin "2") (pinfunction "2_2") (pintype "passive"))
      (node (ref "C165") (pin "1") (pinfunction "1_1") (pintype "passive"))
      (node (ref "C166") (pin "2") (pinfunction "2_2") (pintype "passive"))
      (node (ref "C167") (pin "2") (pinfunction "2_2") (pintype "passive"))
      (node (ref "C168") (pin "2") (pinfunction "2_2") (pintype "passive"))
      (node (ref "C169") (pin "2") (pinfunction "2_2") (pintype "passive"))
      (node (ref "C170") (pin "2") (pinfunction "2_2") (pintype "passive"))
      (node (ref "C171") (pin "2") (pinfunction "2_2") (pintype "passive"))
      (node (ref "C172") (pin "1") (pinfunction "1_1") (pintype "passive"))
      (node (ref "C173") (pin "2") (pinfunction "2_2") (pintype "passive"))
      (node (ref "C174") (pin "2") (pinfunction "2_2") (pintype "passive"))
      (node (ref "C175") (pin "1") (pinfunction "1_1") (pintype "passive"))
      (node (ref "C176") (pin "1") (pinfunction "1_1") (pintype "passive"))
      (node (ref "C177") (pin "2") (pinfunction "2_2") (pintype "passive"))
      (node (ref "C178") (pin "2") (pinfunction "2_2") (pintype "passive"))
      (node (ref "C179") (pin "2") (pinfunction "2_2") (pintype "passive"))
      (node (ref "C180") (pin "2") (pinfunction "2_2") (pintype "passive"))
      (node (ref "ESD5") (pin "2") (pinfunction "2_2") (pintype "passive"))
      (node (ref "ESD6") (pin "2") (pinfunction "2_2") (pintype "passive"))
      (node (ref "IC10") (pin "2") (pinfunction "GND_2") (pintype "passive"))
      (node (ref "IC11") (pin "1") (pinfunction "GND_1") (pintype "passive"))
      (node (ref "IC11") (pin "16") (pinfunction "GND_16") (pintype "passive"))
      (node (ref "IC11") (pin "2") (pinfunction "GND_2") (pintype "passive"))
      (node (ref "IC11") (pin "4") (pinfunction "GND_4") (pintype "passive"))
      (node (ref "IC11") (pin "5") (pinfunction "GND_5") (pintype "passive"))
      (node (ref "IC12") (pin "5") (pinfunction "DIR3_5") (pintype "passive"))
      (node (ref "IC12") (pin "7") (pinfunction "OE_7") (pintype "passive"))
      (node (ref "IC12") (pin "8") (pinfunction "GND_8") (pintype "passive"))
      (node (ref "IC13") (pin "1") (pinfunction "E0_1") (pintype "input"))
      (node (ref "IC13") (pin "2") (pinfunction "E1_2") (pintype "input"))
      (node (ref "IC13") (pin "3") (pinfunction "E2_3") (pintype "input"))
      (node (ref "IC13") (pin "4") (pinfunction "VSS_4") (pintype "power_in"))
      (node (ref "IC13") (pin "7") (pinfunction "~{WC}_7") (pintype "input"))
      (node (ref "IC13") (pin "PAD") (pinfunction "PAD_PAD") (pintype "power_in"))
      (node (ref "IC14") (pin "11") (pinfunction "A0_11") (pintype "input"))
      (node (ref "IC14") (pin "12") (pinfunction "A1_12") (pintype "input"))
      (node (ref "IC14") (pin "13") (pinfunction "A2_13") (pintype "input"))
      (node (ref "IC14") (pin "2") (pinfunction "GPB5_2") (pintype "bidirectional"))
      (node (ref "IC14") (pin "6") (pinfunction "VSS_6") (pintype "power_in"))
      (node (ref "IC14") (pin "PAD") (pinfunction "GND_PAD") (pintype "passive"))
      (node (ref "IC15") (pin "4") (pinfunction "GND_4") (pintype "passive"))
      (node (ref "IC8") (pin "16") (pinfunction "DIR2_16") (pintype "passive"))
      (node (ref "IC8") (pin "7") (pinfunction "OE_7") (pintype "passive"))
      (node (ref "IC8") (pin "8") (pinfunction "GND_8") (pintype "passive"))
      (node (ref "IC9") (pin "7") (pinfunction "OE_7") (pintype "passive"))
      (node (ref "IC9") (pin "8") (pinfunction "GND_8") (pintype "passive"))
      (node (ref "J2") (pin "2") (pinfunction "Y_2") (pintype "passive"))
      (node (ref "R130") (pin "2") (pinfunction "2_2") (pintype "passive"))
      (node (ref "R131") (pin "2") (pinfunction "2_2") (pintype "passive"))
      (node (ref "R132") (pin "2") (pinfunction "2_2") (pintype "passive"))
      (node (ref "R133") (pin "2") (pinfunction "2_2") (pintype "passive"))
      (node (ref "R134") (pin "2") (pinfunction "2_2") (pintype "passive"))
      (node (ref "R135") (pin "2") (pinfunction "2_2") (pintype "passive"))
      (node (ref "R136") (pin "2") (pinfunction "2_2") (pintype "passive"))
      (node (ref "R137") (pin "2") (pinfunction "2_2") (pintype "passive"))
      (node (ref "R143") (pin "2") (pinfunction "2_2") (pintype "passive"))
      (node (ref "R144") (pin "2") (pinfunction "2_2") (pintype "passive"))
      (node (ref "R146") (pin "2") (pinfunction "2_2") (pintype "passive"))
      (node (ref "X5") (pin "2") (pinfunction "Y_2") (pintype "passive"))
      (node (ref "X8") (pin "7") (pinfunction "7_7") (pintype "passive"))
      (node (ref "X8") (pin "MECH") (pinfunction "GND_MECH") (pintype "passive"))
      (node (ref "X9") (pin "MOUNTING-HOLE") (pinfunction "MP1_MOUNTING-HOLE") (pintype "bidirectional"))
      (node (ref "X9") (pin "P1") (pinfunction "1_P1") (pintype "bidirectional"))
      (node (ref "X9") (pin "P21") (pinfunction "21_P21") (pintype "bidirectional"))
      (node (ref "X9") (pin "P27") (pinfunction "27_P27") (pintype "bidirectional"))
      (node (ref "X9") (pin "P3") (pinfunction "3_P3") (pintype "bidirectional"))
      (node (ref "X9") (pin "P33") (pinfunction "33_P33") (pintype "bidirectional"))
      (node (ref "X9") (pin "P39") (pinfunction "39_P39") (pintype "bidirectional"))
      (node (ref "X9") (pin "P45") (pinfunction "45_P45") (pintype "bidirectional"))
      (node (ref "X9") (pin "P51") (pinfunction "51_P51") (pintype "bidirectional"))
      (node (ref "X9") (pin "P57") (pinfunction "57_P57") (pintype "bidirectional"))
      (node (ref "X9") (pin "P71") (pinfunction "71_P71") (pintype "bidirectional"))
      (node (ref "X9") (pin "P73") (pinfunction "73_P73") (pintype "bidirectional"))
      (node (ref "X9") (pin "P75") (pinfunction "75_P75") (pintype "bidirectional"))
    )
    (net (code "80") (name "Net-(C167-Pad1)") (class "Default")
      (node (ref "C167") (pin "1") (pinfunction "1_1") (pintype "passive"))
      (node (ref "L1") (pin "2") (pinfunction "2_2") (pintype "passive"))
      (node (ref "R113") (pin "1") (pinfunction "1_1") (pintype "passive"))
    )
    (net (code "81") (name "Net-(C170-Pad1)") (class "Default")
      (node (ref "C170") (pin "1") (pinfunction "1_1") (pintype "passive"))
      (node (ref "FR37") (pin "1") (pinfunction "1_1") (pintype "passive"))
      (node (ref "R114") (pin "2") (pinfunction "2_2") (pintype "passive"))
    )
    (net (code "82") (name "Net-(IC11-UART_RX)") (class "Default")
      (node (ref "FR36") (pin "2") (pinfunction "2_2") (pintype "passive"))
      (node (ref "IC11") (pin "9") (pinfunction "UART_RX_9") (pintype "input"))
    )
    (net (code "83") (name "Net-(IC11-UART_TX)") (class "Default")
      (node (ref "FR37") (pin "2") (pinfunction "2_2") (pintype "passive"))
      (node (ref "IC11") (pin "10") (pinfunction "UART_TX_10") (pintype "output"))
    )
    (net (code "84") (name "Net-(J2-X)") (class "Default")
      (node (ref "ESD6") (pin "1") (pinfunction "1_1") (pintype "passive"))
      (node (ref "J2") (pin "1") (pinfunction "X_1") (pintype "passive"))
      (node (ref "R229") (pin "2") (pinfunction "2_2") (pintype "passive"))
      (node (ref "R230") (pin "2") (pinfunction "2_2") (pintype "passive"))
      (node (ref "R231") (pin "2") (pinfunction "2_2") (pintype "passive"))
      (node (ref "R232") (pin "2") (pinfunction "2_2") (pintype "passive"))
    )
    (net (code "85") (name "Net-(LED1-C)") (class "Default")
      (node (ref "LED1") (pin "K") (pinfunction "C_K") (pintype "power_in"))
      (node (ref "R145") (pin "1") (pinfunction "1_1") (pintype "passive"))
    )
    (net (code "86") (name "Net-(LED2-C)") (class "Default")
      (node (ref "LED2") (pin "K") (pinfunction "C_K") (pintype "power_in"))
      (node (ref "R148") (pin "1") (pinfunction "1_1") (pintype "passive"))
    )
    (net (code "87") (name "VCC1P8") (class "Default")
      (node (ref "C163") (pin "2") (pinfunction "2_2") (pintype "passive"))
      (node (ref "C165") (pin "2") (pinfunction "2_2") (pintype "passive"))
      (node (ref "C172") (pin "2") (pinfunction "2_2") (pintype "passive"))
      (node (ref "IC12") (pin "14") (pinfunction "VCCA_14") (pintype "passive"))
      (node (ref "IC12") (pin "15") (pinfunction "DIR1_15") (pintype "passive"))
      (node (ref "IC12") (pin "16") (pinfunction "DIR2_16") (pintype "passive"))
      (node (ref "IC12") (pin "6") (pinfunction "DIR4_6") (pintype "passive"))
      (node (ref "IC8") (pin "14") (pinfunction "VCCA_14") (pintype "passive"))
      (node (ref "IC8") (pin "15") (pinfunction "DIR1_15") (pintype "passive"))
      (node (ref "IC8") (pin "5") (pinfunction "DIR3_5") (pintype "passive"))
      (node (ref "IC8") (pin "6") (pinfunction "DIR4_6") (pintype "passive"))
      (node (ref "IC9") (pin "14") (pinfunction "VCCA_14") (pintype "passive"))
      (node (ref "IC9") (pin "15") (pinfunction "DIR1_15") (pintype "passive"))
      (node (ref "IC9") (pin "16") (pinfunction "DIR2_16") (pintype "passive"))
      (node (ref "IC9") (pin "5") (pinfunction "DIR3_5") (pintype "passive"))
      (node (ref "IC9") (pin "6") (pinfunction "DIR4_6") (pintype "passive"))
      (node (ref "JP1") (pin "2") (pinfunction "2_2") (pintype "passive"))
      (node (ref "R116") (pin "1") (pinfunction "1_1") (pintype "passive"))
      (node (ref "R117") (pin "1") (pinfunction "1_1") (pintype "passive"))
      (node (ref "R118") (pin "1") (pinfunction "1_1") (pintype "passive"))
      (node (ref "R119") (pin "1") (pinfunction "1_1") (pintype "passive"))
      (node (ref "R121") (pin "1") (pinfunction "1_1") (pintype "passive"))
      (node (ref "R122") (pin "1") (pinfunction "1_1") (pintype "passive"))
      (node (ref "R123") (pin "1") (pinfunction "1_1") (pintype "passive"))
      (node (ref "R124") (pin "1") (pinfunction "1_1") (pintype "passive"))
      (node (ref "R125") (pin "1") (pinfunction "1_1") (pintype "passive"))
      (node (ref "R126") (pin "1") (pinfunction "1_1") (pintype "passive"))
      (node (ref "R127") (pin "1") (pinfunction "1_1") (pintype "passive"))
      (node (ref "R128") (pin "1") (pinfunction "1_1") (pintype "passive"))
      (node (ref "R147") (pin "1") (pinfunction "1_1") (pintype "passive"))
      (node (ref "VT1") (pin "G") (pinfunction "G_G") (pintype "passive"))
      (node (ref "VT2") (pin "G") (pinfunction "G_G") (pintype "passive"))
    )
    (net (code "88") (name "VCC3P3") (class "Default")
      (node (ref "C164") (pin "1") (pinfunction "1_1") (pintype "passive"))
      (node (ref "C166") (pin "1") (pinfunction "1_1") (pintype "passive"))
      (node (ref "C168") (pin "1") (pinfunction "1_1") (pintype "passive"))
      (node (ref "C173") (pin "1") (pinfunction "1_1") (pintype "passive"))
      (node (ref "C177") (pin "1") (pinfunction "1_1") (pintype "passive"))
      (node (ref "C179") (pin "1") (pinfunction "1_1") (pintype "passive"))
      (node (ref "C180") (pin "1") (pinfunction "1_1") (pintype "passive"))
      (node (ref "FR38") (pin "1") (pinfunction "1_1") (pintype "passive"))
      (node (ref "IC10") (pin "5") (pinfunction "V+_5") (pintype "power_in"))
      (node (ref "IC12") (pin "13") (pinfunction "VCCB_13") (pintype "passive"))
      (node (ref "IC13") (pin "8") (pinfunction "VCC_8") (pintype "power_in"))
      (node (ref "IC14") (pin "5") (pinfunction "VDD_5") (pintype "power_in"))
      (node (ref "IC15") (pin "8") (pinfunction "VCC_8") (pintype "power_in"))
      (node (ref "IC8") (pin "13") (pinfunction "VCCB_13") (pintype "passive"))
      (node (ref "IC9") (pin "13") (pinfunction "VCCB_13") (pintype "passive"))
      (node (ref "LED1") (pin "A") (pinfunction "A_A") (pintype "power_in"))
      (node (ref "LED2") (pin "A") (pinfunction "A_A") (pintype "power_in"))
      (node (ref "R115") (pin "1") (pinfunction "1_1") (pintype "passive"))
      (node (ref "R120") (pin "1") (pinfunction "1_1") (pintype "passive"))
      (node (ref "R139") (pin "1") (pinfunction "1_1") (pintype "passive"))
      (node (ref "R149") (pin "1") (pinfunction "1_1") (pintype "passive"))
      (node (ref "X8") (pin "1") (pinfunction "1_1") (pintype "passive"))
    )
    (net (code "89") (name "VCC3P3_GNSS") (class "Default")
      (node (ref "C175") (pin "2") (pinfunction "2_2") (pintype "passive"))
      (node (ref "C176") (pin "2") (pinfunction "2_2") (pintype "passive"))
      (node (ref "FR38") (pin "2") (pinfunction "2_2") (pintype "passive"))
      (node (ref "IC11") (pin "14") (pinfunction "BV_14") (pintype "power_in"))
      (node (ref "IC11") (pin "15") (pinfunction "VCC_15") (pintype "power_in"))
      (node (ref "R113") (pin "2") (pinfunction "2_2") (pintype "passive"))
    )
    (net (code "90") (name "VCC3P3_M.2") (class "Default")
      (node (ref "X9") (pin "P2") (pinfunction "2_P2") (pintype "bidirectional"))
      (node (ref "X9") (pin "P4") (pinfunction "4_P4") (pintype "bidirectional"))
      (node (ref "X9") (pin "P70") (pinfunction "70_P70") (pintype "bidirectional"))
      (node (ref "X9") (pin "P72") (pinfunction "72_P72") (pintype "bidirectional"))
      (node (ref "X9") (pin "P74") (pinfunction "74_P74") (pintype "bidirectional"))
    )
    (net (code "91") (name "unconnected-(IC10-ALERT-Pad3)") (class "Default")
      (node (ref "IC10") (pin "3") (pinfunction "ALERT_3") (pintype "output+no_connect"))
    )
    (net (code "92") (name "unconnected-(IC11-E2-Pad11)") (class "Default")
      (node (ref "IC11") (pin "11") (pinfunction "E2_11") (pintype "passive+no_connect"))
    )
    (net (code "93") (name "unconnected-(IC11-E3-Pad12)") (class "Default")
      (node (ref "IC11") (pin "12") (pinfunction "E3_12") (pintype "passive+no_connect"))
    )
    (net (code "94") (name "unconnected-(IC14-GPB6-Pad3)") (class "Default")
      (node (ref "IC14") (pin "3") (pinfunction "GPB6_3") (pintype "bidirectional+no_connect"))
    )
    (net (code "95") (name "unconnected-(IC14-INTA-Pad16)") (class "Default")
      (node (ref "IC14") (pin "16") (pinfunction "INTA_16") (pintype "open_collector+no_connect"))
    )
    (net (code "96") (name "unconnected-(IC14-INTB-Pad15)") (class "Default")
      (node (ref "IC14") (pin "15") (pinfunction "INTB_15") (pintype "open_collector+no_connect"))
    )
    (net (code "97") (name "unconnected-(IC14-NC-Pad7)") (class "Default")
      (node (ref "IC14") (pin "7") (pinfunction "NC_7") (pintype "passive+no_connect"))
    )
    (net (code "98") (name "unconnected-(IC14-NC-Pad10)") (class "Default")
      (node (ref "IC14") (pin "10") (pinfunction "NC_10") (pintype "passive+no_connect"))
    )
    (net (code "99") (name "unconnected-(IC15-NC-Pad1)") (class "Default")
      (node (ref "IC15") (pin "1") (pinfunction "NC_1") (pintype "passive+no_connect"))
    )
    (net (code "100") (name "unconnected-(IC15-NC-Pad2)") (class "Default")
      (node (ref "IC15") (pin "2") (pinfunction "NC_2") (pintype "passive+no_connect"))
    )
    (net (code "101") (name "unconnected-(IC15-NC-Pad3)") (class "Default")
      (node (ref "IC15") (pin "3") (pinfunction "NC_3") (pintype "passive+no_connect"))
    )
    (net (code "102") (name "unconnected-(IC15-NC-Pad7)") (class "Default")
      (node (ref "IC15") (pin "7") (pinfunction "NC_7") (pintype "passive+no_connect"))
    )
    (net (code "103") (name "unconnected-(JMP1-Pad1)") (class "Default")
      (node (ref "JMP1") (pin "1") (pinfunction "1_1") (pintype "passive"))
    )
    (net (code "104") (name "unconnected-(JMP1-Pad2)") (class "Default")
      (node (ref "JMP1") (pin "2") (pinfunction "2_2") (pintype "passive"))
    )
    (net (code "105") (name "unconnected-(X9A-5-PadP5)") (class "Default")
      (node (ref "X9") (pin "P5") (pinfunction "5_P5") (pintype "bidirectional+no_connect"))
    )
    (net (code "106") (name "unconnected-(X9A-7-PadP7)") (class "Default")
      (node (ref "X9") (pin "P7") (pinfunction "7_P7") (pintype "bidirectional+no_connect"))
    )
    (net (code "107") (name "unconnected-(X9A-9-PadP9)") (class "Default")
      (node (ref "X9") (pin "P9") (pinfunction "9_P9") (pintype "bidirectional+no_connect"))
    )
    (net (code "108") (name "unconnected-(X9A-11-PadP11)") (class "Default")
      (node (ref "X9") (pin "P11") (pinfunction "11_P11") (pintype "bidirectional+no_connect"))
    )
    (net (code "109") (name "unconnected-(X9A-23-PadP23)") (class "Default")
      (node (ref "X9") (pin "P23") (pinfunction "23_P23") (pintype "bidirectional+no_connect"))
    )
    (net (code "110") (name "unconnected-(X9A-25-PadP25)") (class "Default")
      (node (ref "X9") (pin "P25") (pinfunction "25_P25") (pintype "bidirectional+no_connect"))
    )
    (net (code "111") (name "unconnected-(X9A-29-PadP29)") (class "Default")
      (node (ref "X9") (pin "P29") (pinfunction "29_P29") (pintype "bidirectional+no_connect"))
    )
    (net (code "112") (name "unconnected-(X9A-31-PadP31)") (class "Default")
      (node (ref "X9") (pin "P31") (pinfunction "31_P31") (pintype "bidirectional+no_connect"))
    )
    (net (code "113") (name "unconnected-(X9A-35-PadP35)") (class "Default")
      (node (ref "X9") (pin "P35") (pinfunction "35_P35") (pintype "bidirectional+no_connect"))
    )
    (net (code "114") (name "unconnected-(X9A-37-PadP37)") (class "Default")
      (node (ref "X9") (pin "P37") (pinfunction "37_P37") (pintype "bidirectional+no_connect"))
    )
    (net (code "115") (name "unconnected-(X9A-67-PadP67)") (class "Default")
      (node (ref "X9") (pin "P67") (pinfunction "67_P67") (pintype "bidirectional+no_connect"))
    )
    (net (code "116") (name "unconnected-(X9A-69-PadP69)") (class "Default")
      (node (ref "X9") (pin "P69") (pinfunction "69_P69") (pintype "bidirectional+no_connect"))
    )
    (net (code "117") (name "unconnected-(X9B-6-PadP6)") (class "Default")
      (node (ref "X9") (pin "P6") (pinfunction "6_P6") (pintype "bidirectional+no_connect"))
    )
    (net (code "118") (name "unconnected-(X9B-30-PadP30)") (class "Default")
      (node (ref "X9") (pin "P30") (pinfunction "30_P30") (pintype "bidirectional+no_connect"))
    )
    (net (code "119") (name "unconnected-(X9B-32-PadP32)") (class "Default")
      (node (ref "X9") (pin "P32") (pinfunction "32_P32") (pintype "bidirectional+no_connect"))
    )
    (net (code "120") (name "unconnected-(X9B-34-PadP34)") (class "Default")
      (node (ref "X9") (pin "P34") (pinfunction "34_P34") (pintype "bidirectional+no_connect"))
    )
    (net (code "121") (name "unconnected-(X9B-36-PadP36)") (class "Default")
      (node (ref "X9") (pin "P36") (pinfunction "36_P36") (pintype "bidirectional+no_connect"))
    )
    (net (code "122") (name "unconnected-(X9B-38-PadP38)") (class "Default")
      (node (ref "X9") (pin "P38") (pinfunction "38_P38") (pintype "bidirectional+no_connect"))
    )
    (net (code "123") (name "unconnected-(X9B-54-PadP54)") (class "Default")
      (node (ref "X9") (pin "P54") (pinfunction "54_P54") (pintype "bidirectional+no_connect"))
    )
    (net (code "124") (name "unconnected-(X9B-68-PadP68)") (class "Default")
      (node (ref "X9") (pin "P68") (pinfunction "68_P68") (pintype "bidirectional+no_connect"))
    )
  )
)
